# loop_2_SMA.net
KiCad netlist of a schematic drawn in Altium Designer
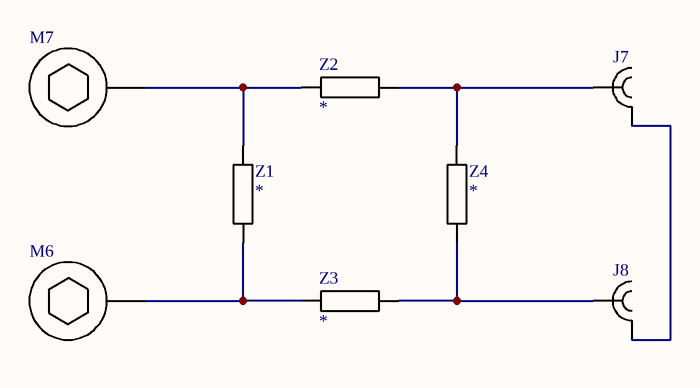
[diagram p0: loop_2_SMA.SchDoc]

(export (version "E")
  (design (tool "Eeschema 10.0.6"))
  (components
    (comp (ref "J7")
      (value "CONSMA001-G")
      (footprint "SMA TH Vertical Linx CONSMA001-G")
      (description "SMA TH VERTICAL LINX CONSMA001-G")
      (libsource (lib "Connector") (part "SMA TH VERTICAL LINX CONSMA001-G"))
    )
    (comp (ref "J8")
      (value "CONSMA001-G")
      (footprint "SMA TH Vertical Linx CONSMA001-G")
      (description "SMA TH VERTICAL LINX CONSMA001-G")
      (libsource (lib "Connector") (part "SMA TH VERTICAL LINX CONSMA001-G"))
    )
    (comp (ref "M6")
      (value "~")
      (footprint "Screw Hex Socket M2.5X4 Connected")
      (description "Screw Hex Socket Connected BN610")
      (libsource (lib "Mechanic") (part "Screw Hex Socket Connected"))
    )
    (comp (ref "M7")
      (value "~")
      (footprint "Screw Hex Socket M2.5X4 Connected")
      (description "Screw Hex Socket Connected BN610")
      (libsource (lib "Mechanic") (part "Screw Hex Socket Connected"))
    )
    (comp (ref "Z1")
      (value "*")
      (footprint "RESISTOR 2012 REFLOW")
      (description "Resistor")
      (libsource (lib "Resistor") (part "Resistor"))
    )
    (comp (ref "Z2")
      (value "*")
      (footprint "RESISTOR 2012 REFLOW")
      (description "Resistor")
      (libsource (lib "Resistor") (part "Resistor"))
    )
    (comp (ref "Z3")
      (value "*")
      (footprint "RESISTOR 2012 REFLOW")
      (description "Resistor")
      (libsource (lib "Resistor") (part "Resistor"))
    )
    (comp (ref "Z4")
      (value "*")
      (footprint "RESISTOR 2012 REFLOW")
      (description "Resistor")
      (libsource (lib "Resistor") (part "Resistor"))
    )
  )
  (nets
    (net (code "1") (name "Net-(J7-Pad1)") (class "Default")
      (node (ref "J7") (pin "1") (pinfunction "1_1") (pintype "passive"))
      (node (ref "Z2") (pin "2") (pinfunction "2_2") (pintype "passive"))
      (node (ref "Z4") (pin "2") (pinfunction "2_2") (pintype "passive"))
    )
    (net (code "2") (name "Net-(J7-Pad2)") (class "Default")
      (node (ref "J7") (pin "2") (pinfunction "2_2") (pintype "passive"))
      (node (ref "J8") (pin "2") (pinfunction "2_2") (pintype "passive"))
    )
    (net (code "3") (name "Net-(J8-Pad1)") (class "Default")
      (node (ref "J8") (pin "1") (pinfunction "1_1") (pintype "passive"))
      (node (ref "Z3") (pin "2") (pinfunction "2_2") (pintype "passive"))
      (node (ref "Z4") (pin "1") (pinfunction "1_1") (pintype "passive"))
    )
    (net (code "4") (name "Net-(M6-Pad1)") (class "Default")
      (node (ref "M6") (pin "1") (pinfunction "1_1") (pintype "passive"))
      (node (ref "Z1") (pin "1") (pinfunction "1_1") (pintype "passive"))
      (node (ref "Z3") (pin "1") (pinfunction "1_1") (pintype "passive"))
    )
    (net (code "5") (name "Net-(M7-Pad1)") (class "Default")
      (node (ref "M7") (pin "1") (pinfunction "1_1") (pintype "passive"))
      (node (ref "Z1") (pin "2") (pinfunction "2_2") (pintype "passive"))
      (node (ref "Z2") (pin "1") (pinfunction "1_1") (pintype "passive"))
    )
  )
)
